# MTX_Tap_an_er_V12_Nopoti.net
KiCad netlist of a schematic drawn in EAGLE
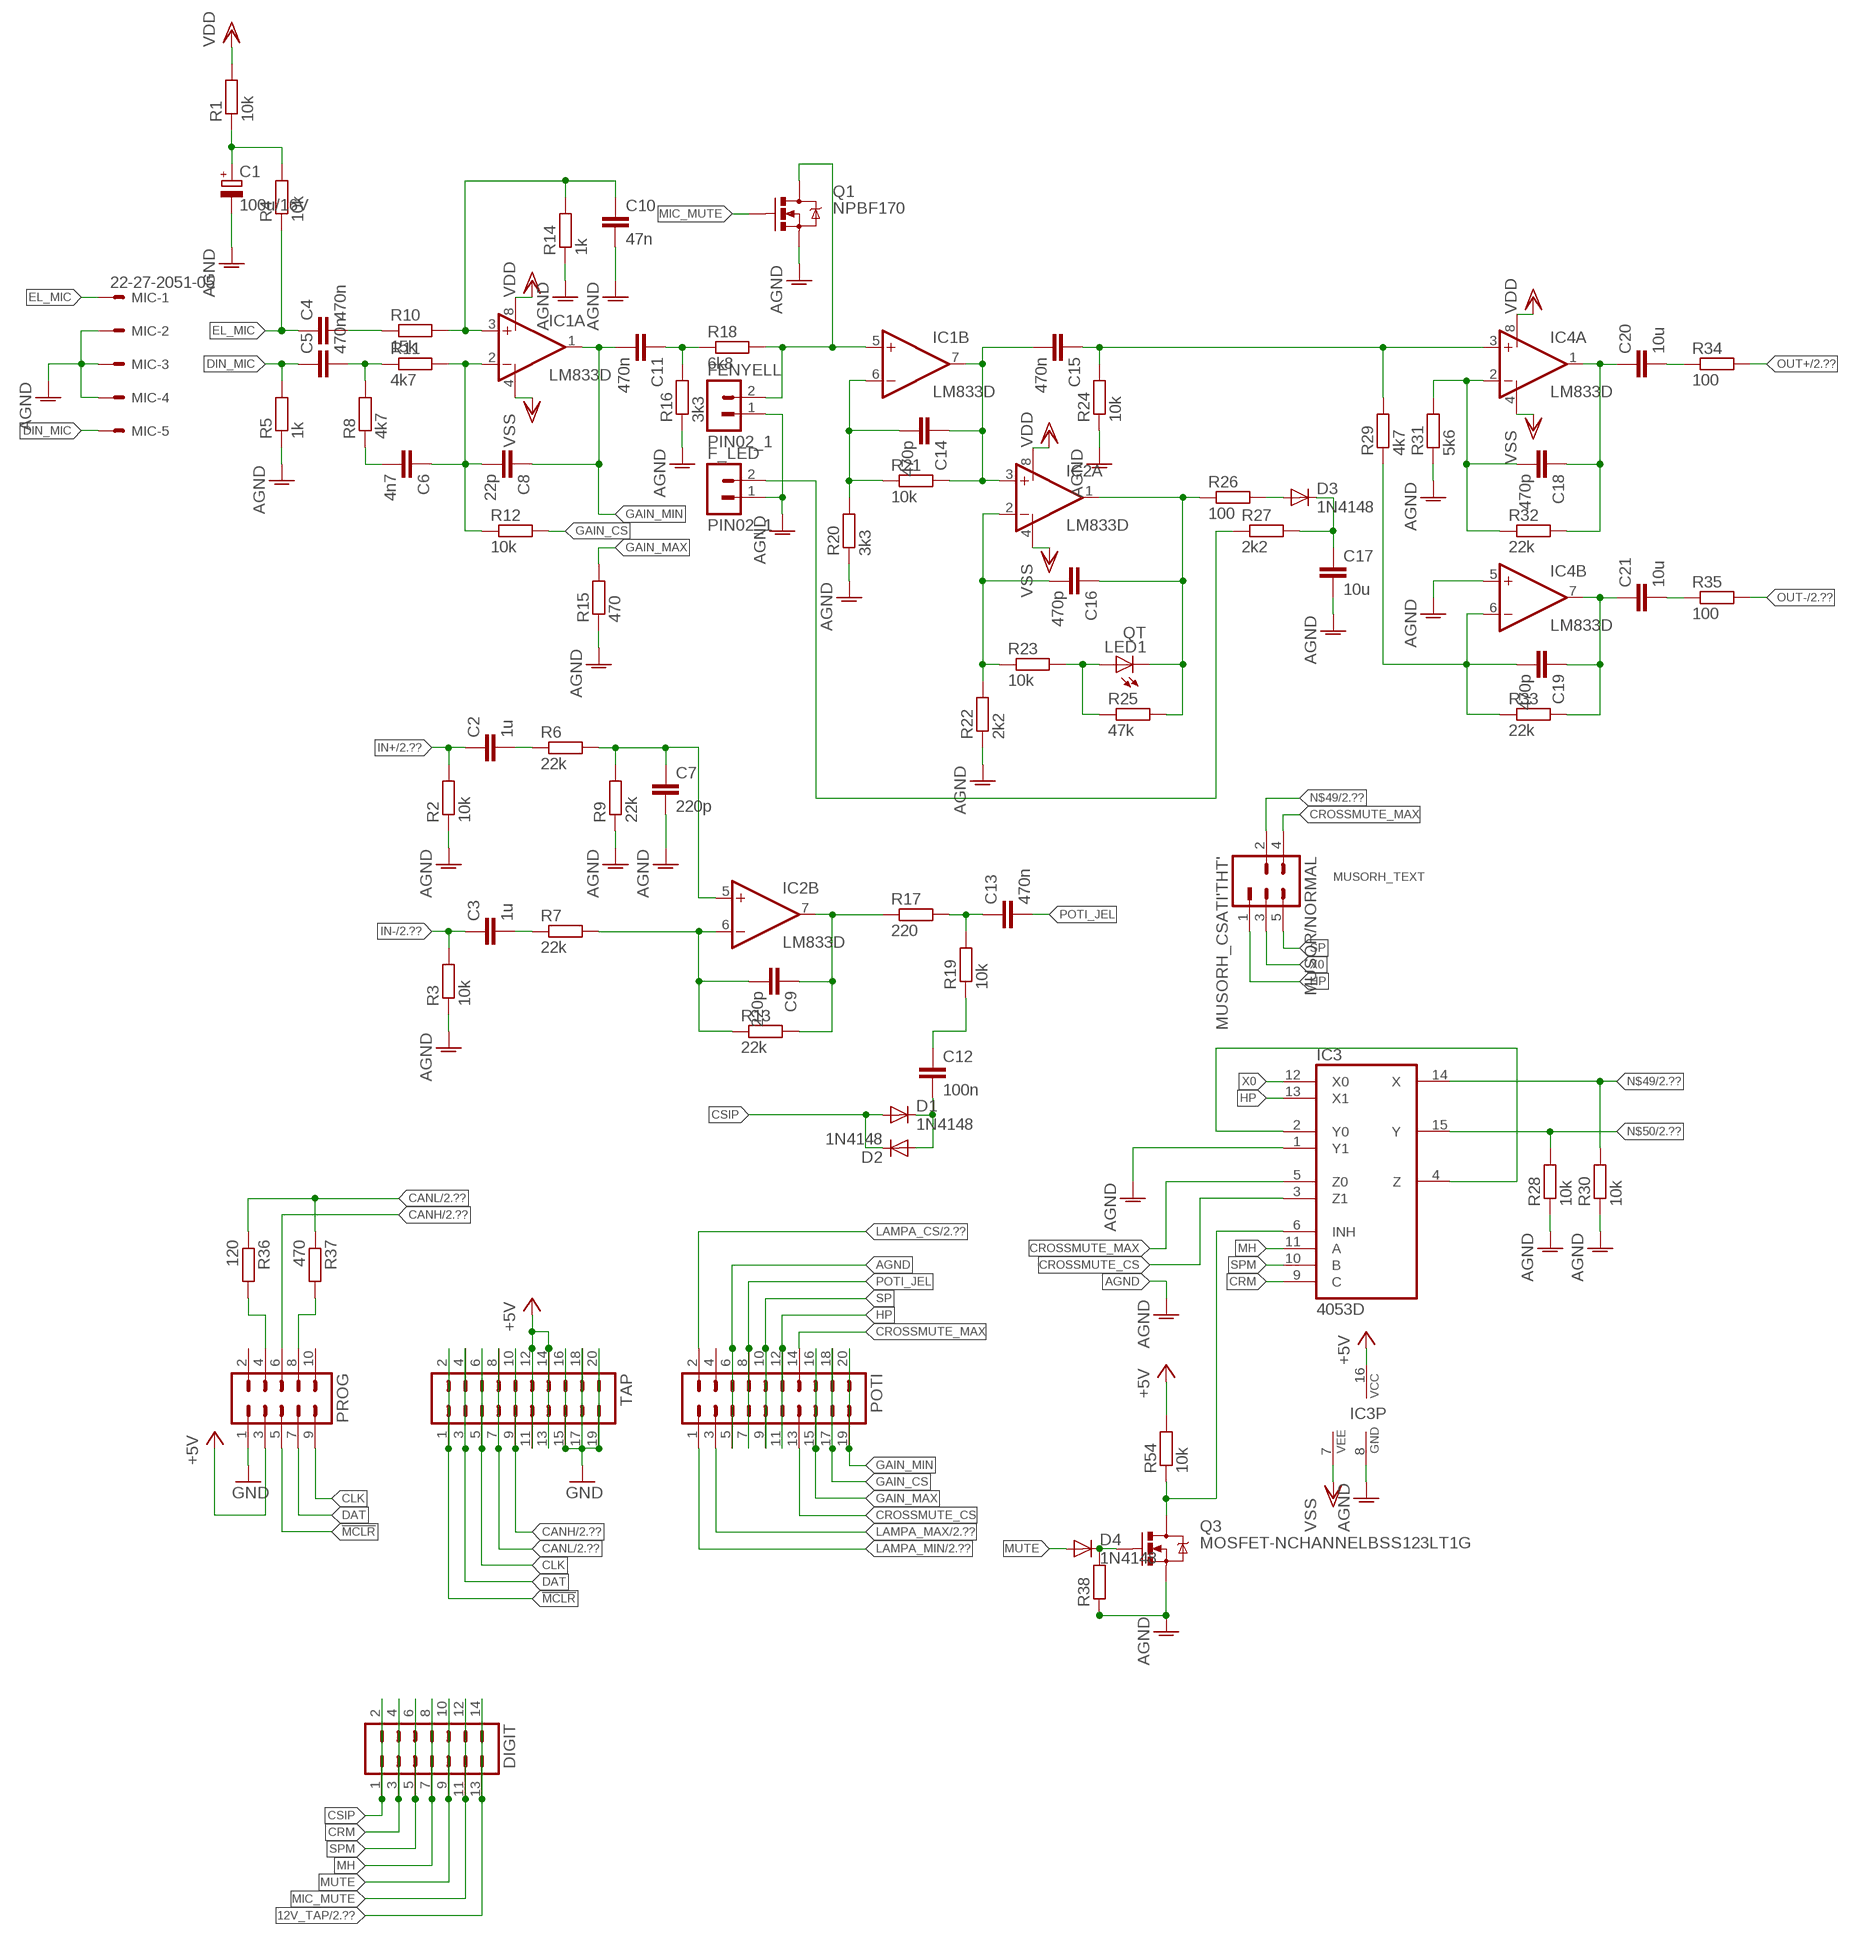
[diagram p0: schematic, sheet 1]
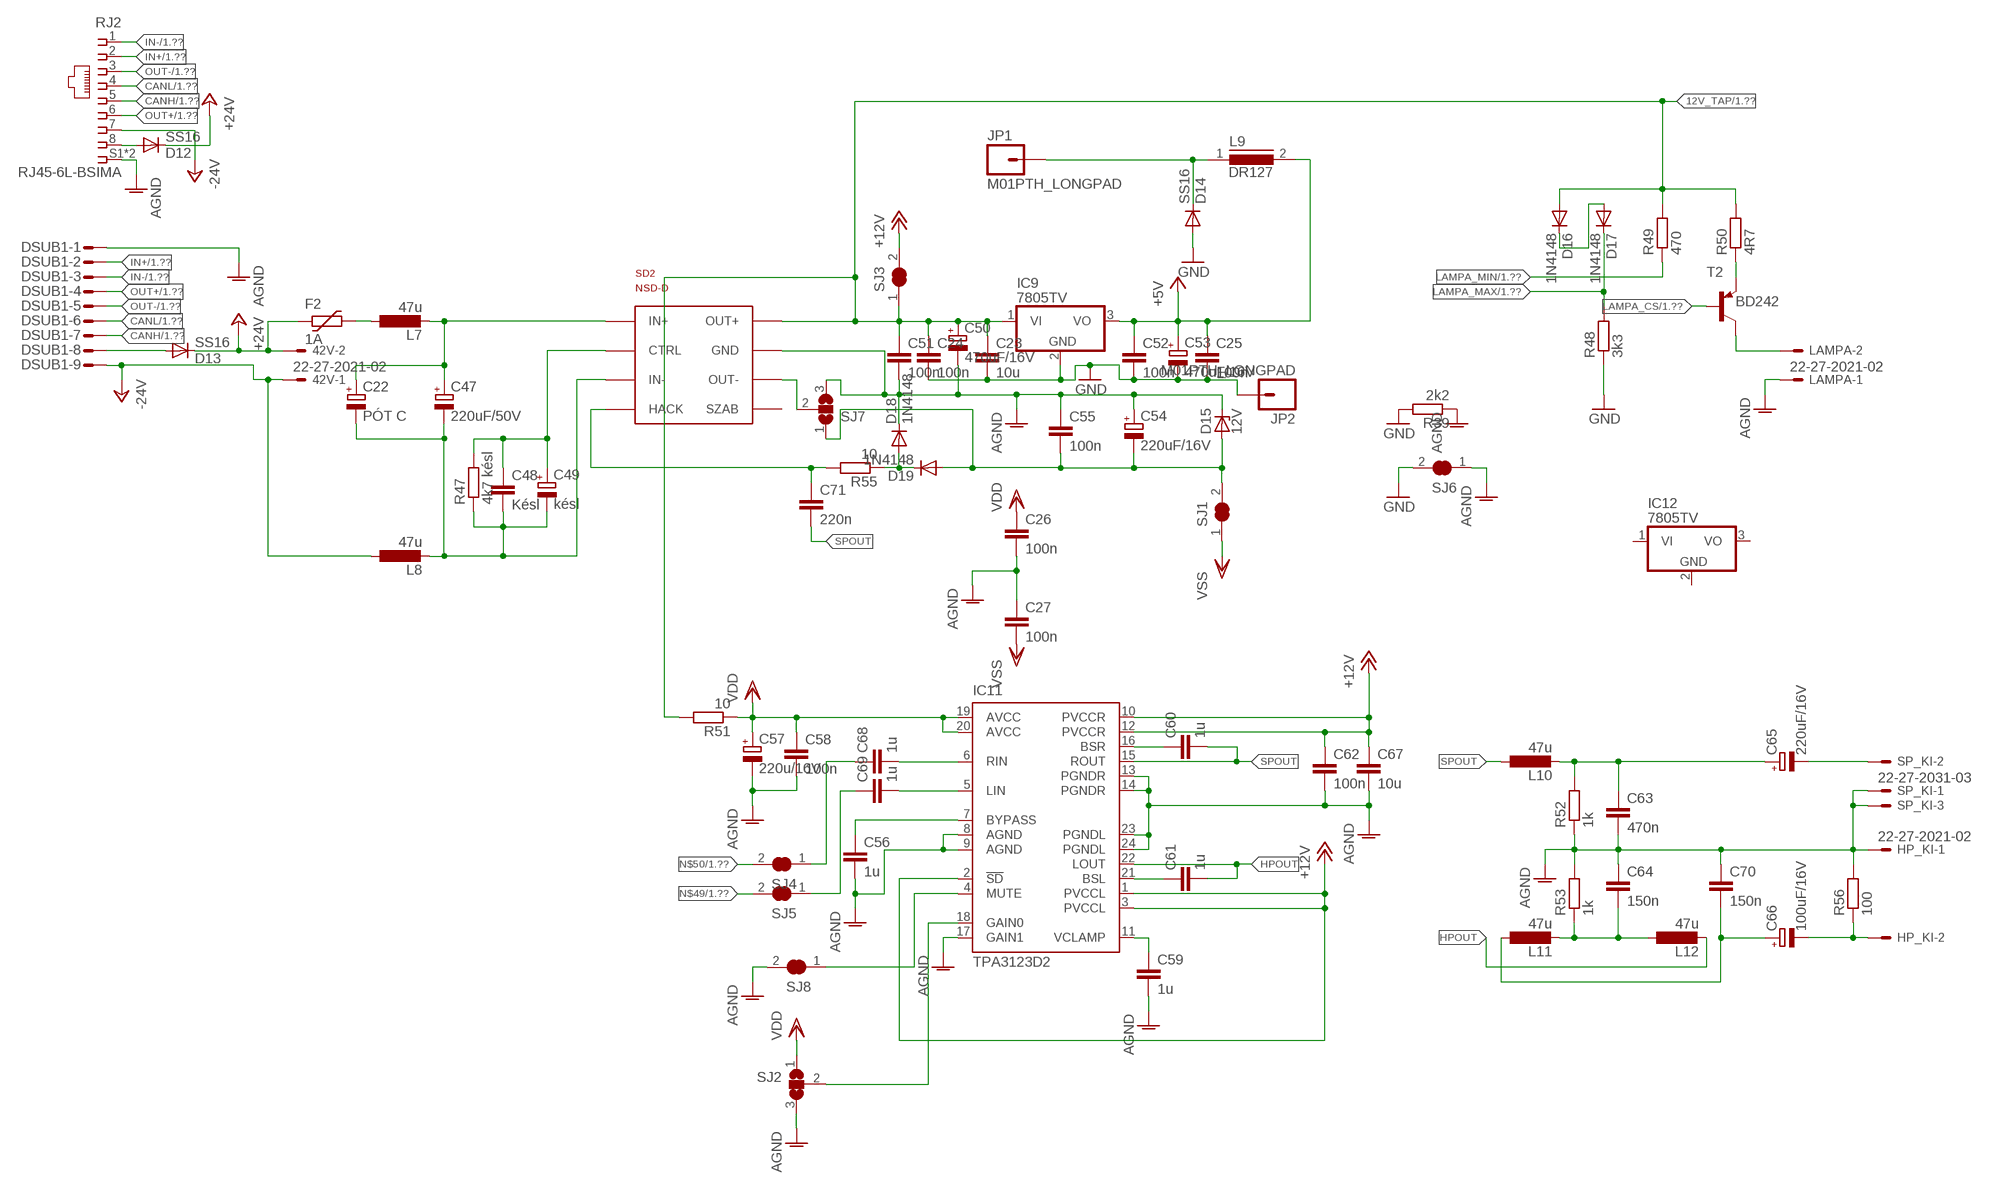
[diagram p1: schematic, sheet 2]

(export (version "E")
  (design (tool "Eeschema 10.0.6"))
  (components
    (comp (ref "C1")
      (value "100u/16V")
      (footprint "eagle-import:E2,5-5")
      (libsource (lib "eagle-import") (part "CPOL-EUE2.5-5"))
    )
    (comp (ref "C2")
      (value "1u")
      (footprint "eagle-import:C0805")
      (libsource (lib "eagle-import") (part "C-EUC0805"))
    )
    (comp (ref "C3")
      (value "1u")
      (footprint "eagle-import:C0805")
      (libsource (lib "eagle-import") (part "C-EUC0805"))
    )
    (comp (ref "C4")
      (value "470n")
      (footprint "eagle-import:C0805")
      (libsource (lib "eagle-import") (part "C-EUC0805"))
    )
    (comp (ref "C5")
      (value "470n")
      (footprint "eagle-import:C0805")
      (libsource (lib "eagle-import") (part "C-EUC0805"))
    )
    (comp (ref "C6")
      (value "4n7")
      (footprint "eagle-import:C0805")
      (libsource (lib "eagle-import") (part "C-EUC0805"))
    )
    (comp (ref "C7")
      (value "220p")
      (footprint "eagle-import:C0805")
      (libsource (lib "eagle-import") (part "C-EUC0805"))
    )
    (comp (ref "C8")
      (value "22p")
      (footprint "eagle-import:C0805")
      (libsource (lib "eagle-import") (part "C-EUC0805"))
    )
    (comp (ref "C9")
      (value "220p")
      (footprint "eagle-import:C0805")
      (libsource (lib "eagle-import") (part "C-EUC0805"))
    )
    (comp (ref "C10")
      (value "47n")
      (footprint "eagle-import:C0805")
      (libsource (lib "eagle-import") (part "C-EUC0805"))
    )
    (comp (ref "C11")
      (value "470n")
      (footprint "eagle-import:C0805")
      (libsource (lib "eagle-import") (part "C-EUC0805"))
    )
    (comp (ref "C12")
      (value "100n")
      (footprint "eagle-import:C0805")
      (libsource (lib "eagle-import") (part "C-EUC0805"))
    )
    (comp (ref "C13")
      (value "470n")
      (footprint "eagle-import:C0805")
      (libsource (lib "eagle-import") (part "C-EUC0805"))
    )
    (comp (ref "C14")
      (value "470p")
      (footprint "eagle-import:C0805")
      (libsource (lib "eagle-import") (part "C-EUC0805"))
    )
    (comp (ref "C15")
      (value "470n")
      (footprint "eagle-import:C0805")
      (libsource (lib "eagle-import") (part "C-EUC0805"))
    )
    (comp (ref "C16")
      (value "470p")
      (footprint "eagle-import:C0805")
      (libsource (lib "eagle-import") (part "C-EUC0805"))
    )
    (comp (ref "C17")
      (value "10u")
      (footprint "eagle-import:C0805")
      (libsource (lib "eagle-import") (part "C-EUC0805"))
    )
    (comp (ref "C18")
      (value "470p")
      (footprint "eagle-import:C0805")
      (libsource (lib "eagle-import") (part "C-EUC0805"))
    )
    (comp (ref "C19")
      (value "470p")
      (footprint "eagle-import:C0805")
      (libsource (lib "eagle-import") (part "C-EUC0805"))
    )
    (comp (ref "C20")
      (value "10u")
      (footprint "eagle-import:C0805")
      (libsource (lib "eagle-import") (part "C-EUC0805"))
    )
    (comp (ref "C21")
      (value "10u")
      (footprint "eagle-import:C0805")
      (libsource (lib "eagle-import") (part "C-EUC0805"))
    )
    (comp (ref "D1")
      (value "1N4148")
      (footprint "eagle-import:SOD80C")
      (libsource (lib "eagle-import") (part "DIODE-SOD80C"))
    )
    (comp (ref "D2")
      (value "1N4148")
      (footprint "eagle-import:SOD80C")
      (libsource (lib "eagle-import") (part "DIODE-SOD80C"))
    )
    (comp (ref "D3")
      (value "1N4148")
      (footprint "eagle-import:SOD80C")
      (libsource (lib "eagle-import") (part "DIODE-SOD80C"))
    )
    (comp (ref "D4")
      (value "1N4148")
      (footprint "eagle-import:SOD80C")
      (libsource (lib "eagle-import") (part "DIODE-SOD80C"))
    )
    (comp (ref "DIGIT")
      (value "MA07-2")
      (footprint "eagle-import:MA07-2")
      (libsource (lib "eagle-import") (part "MA07-2"))
    )
    (comp (ref "FENYELL")
      (value "PIN02_1")
      (footprint "eagle-import:PIN02_1")
      (libsource (lib "eagle-import") (part "PIN02_1"))
    )
    (comp (ref "F_LED")
      (value "PIN02_1")
      (footprint "eagle-import:PIN02_1")
      (libsource (lib "eagle-import") (part "PIN02_1"))
    )
    (comp (ref "IC1")
      (value "LM833D")
      (footprint "eagle-import:SO08")
      (libsource (lib "eagle-import") (part "LM833D"))
    )
    (comp (ref "IC2")
      (value "LM833D")
      (footprint "eagle-import:SO08")
      (libsource (lib "eagle-import") (part "LM833D"))
    )
    (comp (ref "IC3")
      (value "4053D")
      (footprint "eagle-import:SO16")
      (libsource (lib "eagle-import") (part "4053D"))
    )
    (comp (ref "IC4")
      (value "LM833D")
      (footprint "eagle-import:SO08")
      (libsource (lib "eagle-import") (part "LM833D"))
    )
    (comp (ref "LED1")
      (value "QT")
      (footprint "eagle-import:LED3MM")
      (libsource (lib "eagle-import") (part "LED3MM"))
    )
    (comp (ref "MIC")
      (value "22-27-2051-05")
      (footprint "eagle-import:6410-05")
      (libsource (lib "eagle-import") (part "22-?-0527-2051"))
    )
    (comp (ref "MUSOR/NORMAL")
      (value "MUSORH_CSATI'THT'")
      (footprint "eagle-import:MUSORH_CSATI")
      (libsource (lib "eagle-import") (part "MUSORH_CSATI'THT'"))
    )
    (comp (ref "POTI")
      (value "MA10-2")
      (footprint "eagle-import:MA10-2")
      (libsource (lib "eagle-import") (part "MA10-2"))
    )
    (comp (ref "PROG")
      (value "ML10L")
      (footprint "eagle-import:ML10L")
      (libsource (lib "eagle-import") (part "ML10L"))
    )
    (comp (ref "Q1")
      (value "NPBF170")
      (footprint "eagle-import:SOT23")
      (libsource (lib "eagle-import") (part "MOSFET-NCHANNELBSS138"))
    )
    (comp (ref "Q3")
      (value "MOSFET-NCHANNELBSS123LT1G")
      (footprint "eagle-import:SOT23")
      (libsource (lib "eagle-import") (part "MOSFET-NCHANNELBSS123LT1G"))
    )
    (comp (ref "R1")
      (value "10k")
      (footprint "eagle-import:R0805")
      (libsource (lib "eagle-import") (part "R-EU_R0805"))
    )
    (comp (ref "R2")
      (value "10k")
      (footprint "eagle-import:R0805")
      (libsource (lib "eagle-import") (part "R-EU_R0805"))
    )
    (comp (ref "R3")
      (value "10k")
      (footprint "eagle-import:R0805")
      (libsource (lib "eagle-import") (part "R-EU_R0805"))
    )
    (comp (ref "R4")
      (value "10k")
      (footprint "eagle-import:R0805")
      (libsource (lib "eagle-import") (part "R-EU_R0805"))
    )
    (comp (ref "R5")
      (value "1k")
      (footprint "eagle-import:R0805")
      (libsource (lib "eagle-import") (part "R-EU_R0805"))
    )
    (comp (ref "R6")
      (value "22k")
      (footprint "eagle-import:R0805")
      (libsource (lib "eagle-import") (part "R-EU_R0805"))
    )
    (comp (ref "R7")
      (value "22k")
      (footprint "eagle-import:R0805")
      (libsource (lib "eagle-import") (part "R-EU_R0805"))
    )
    (comp (ref "R8")
      (value "4k7")
      (footprint "eagle-import:R0805")
      (libsource (lib "eagle-import") (part "R-EU_R0805"))
    )
    (comp (ref "R9")
      (value "22k")
      (footprint "eagle-import:R0805")
      (libsource (lib "eagle-import") (part "R-EU_R0805"))
    )
    (comp (ref "R10")
      (value "15k")
      (footprint "eagle-import:R0805")
      (libsource (lib "eagle-import") (part "R-EU_R0805"))
    )
    (comp (ref "R11")
      (value "4k7")
      (footprint "eagle-import:R0805")
      (libsource (lib "eagle-import") (part "R-EU_R0805"))
    )
    (comp (ref "R12")
      (value "10k")
      (footprint "eagle-import:R0805")
      (libsource (lib "eagle-import") (part "R-EU_R0805"))
    )
    (comp (ref "R13")
      (value "22k")
      (footprint "eagle-import:R0805")
      (libsource (lib "eagle-import") (part "R-EU_R0805"))
    )
    (comp (ref "R14")
      (value "1k")
      (footprint "eagle-import:R0805")
      (libsource (lib "eagle-import") (part "R-EU_R0805"))
    )
    (comp (ref "R15")
      (value "470")
      (footprint "eagle-import:R0805")
      (libsource (lib "eagle-import") (part "R-EU_R0805"))
    )
    (comp (ref "R16")
      (value "3k3")
      (footprint "eagle-import:R0805")
      (libsource (lib "eagle-import") (part "R-EU_R0805"))
    )
    (comp (ref "R17")
      (value "220")
      (footprint "eagle-import:R0805")
      (libsource (lib "eagle-import") (part "R-EU_R0805"))
    )
    (comp (ref "R18")
      (value "6k8")
      (footprint "eagle-import:R0805")
      (libsource (lib "eagle-import") (part "R-EU_R0805"))
    )
    (comp (ref "R19")
      (value "10k")
      (footprint "eagle-import:R0805")
      (libsource (lib "eagle-import") (part "R-EU_R0805"))
    )
    (comp (ref "R20")
      (value "3k3")
      (footprint "eagle-import:R0805")
      (libsource (lib "eagle-import") (part "R-EU_R0805"))
    )
    (comp (ref "R21")
      (value "10k")
      (footprint "eagle-import:R0805")
      (libsource (lib "eagle-import") (part "R-EU_R0805"))
    )
    (comp (ref "R22")
      (value "2k2")
      (footprint "eagle-import:R0805")
      (libsource (lib "eagle-import") (part "R-EU_R0805"))
    )
    (comp (ref "R23")
      (value "10k")
      (footprint "eagle-import:R0805")
      (libsource (lib "eagle-import") (part "R-EU_R0805"))
    )
    (comp (ref "R24")
      (value "10k")
      (footprint "eagle-import:R0805")
      (libsource (lib "eagle-import") (part "R-EU_R0805"))
    )
    (comp (ref "R25")
      (value "47k")
      (footprint "eagle-import:R0805")
      (libsource (lib "eagle-import") (part "R-EU_R0805"))
    )
    (comp (ref "R26")
      (value "100")
      (footprint "eagle-import:R0805")
      (libsource (lib "eagle-import") (part "R-EU_R0805"))
    )
    (comp (ref "R27")
      (value "2k2")
      (footprint "eagle-import:R0805")
      (libsource (lib "eagle-import") (part "R-EU_R0805"))
    )
    (comp (ref "R28")
      (value "10k")
      (footprint "eagle-import:R0805")
      (libsource (lib "eagle-import") (part "R-EU_R0805"))
    )
    (comp (ref "R29")
      (value "4k7")
      (footprint "eagle-import:R0805")
      (libsource (lib "eagle-import") (part "R-EU_R0805"))
    )
    (comp (ref "R30")
      (value "10k")
      (footprint "eagle-import:R0805")
      (libsource (lib "eagle-import") (part "R-EU_R0805"))
    )
    (comp (ref "R31")
      (value "5k6")
      (footprint "eagle-import:R0805")
      (libsource (lib "eagle-import") (part "R-EU_R0805"))
    )
    (comp (ref "R32")
      (value "22k")
      (footprint "eagle-import:R0805")
      (libsource (lib "eagle-import") (part "R-EU_R0805"))
    )
    (comp (ref "R33")
      (value "22k")
      (footprint "eagle-import:R0805")
      (libsource (lib "eagle-import") (part "R-EU_R0805"))
    )
    (comp (ref "R34")
      (value "100")
      (footprint "eagle-import:R0805")
      (libsource (lib "eagle-import") (part "R-EU_R0805"))
    )
    (comp (ref "R35")
      (value "100")
      (footprint "eagle-import:R0805")
      (libsource (lib "eagle-import") (part "R-EU_R0805"))
    )
    (comp (ref "R36")
      (value "120")
      (footprint "eagle-import:R0805")
      (libsource (lib "eagle-import") (part "R-EU_R0805"))
    )
    (comp (ref "R37")
      (value "470")
      (footprint "eagle-import:R0805")
      (libsource (lib "eagle-import") (part "R-EU_R0805"))
    )
    (comp (ref "R38")
      (value "R-EU_R0805")
      (footprint "eagle-import:R0805")
      (libsource (lib "eagle-import") (part "R-EU_R0805"))
    )
    (comp (ref "R54")
      (value "10k")
      (footprint "eagle-import:R0805")
      (libsource (lib "eagle-import") (part "R-EU_R0805"))
    )
    (comp (ref "TAP")
      (value "MA10-2")
      (footprint "eagle-import:MA10-2")
      (libsource (lib "eagle-import") (part "MA10-2"))
    )
    (comp (ref "U$1")
      (value "MUSORH_TEXT")
      (footprint "eagle-import:MUSORH_TEXT")
      (libsource (lib "eagle-import") (part "MUSORH_TEXT"))
    )
    (comp (ref "42V")
      (value "22-27-2021-02")
      (footprint "eagle-import:6410-02")
      (libsource (lib "eagle-import") (part "22-?-0227-2021"))
    )
    (comp (ref "C22")
      (value "PÓT C")
      (footprint "eagle-import:E3,5-8")
      (libsource (lib "eagle-import") (part "CPOL-EUE3.5-8"))
    )
    (comp (ref "C23")
      (value "10u")
      (footprint "eagle-import:C0805")
      (libsource (lib "eagle-import") (part "C-EUC0805"))
    )
    (comp (ref "C24")
      (value "100n")
      (footprint "eagle-import:C0805")
      (libsource (lib "eagle-import") (part "C-EUC0805"))
    )
    (comp (ref "C25")
      (value "100n")
      (footprint "eagle-import:C0805")
      (libsource (lib "eagle-import") (part "C-EUC0805"))
    )
    (comp (ref "C26")
      (value "100n")
      (footprint "eagle-import:C0805")
      (libsource (lib "eagle-import") (part "C-EUC0805"))
    )
    (comp (ref "C27")
      (value "100n")
      (footprint "eagle-import:C0805")
      (libsource (lib "eagle-import") (part "C-EUC0805"))
    )
    (comp (ref "C47")
      (value "220uF/50V")
      (footprint "eagle-import:E3,5-8")
      (libsource (lib "eagle-import") (part "CPOL-EUE3.5-8"))
    )
    (comp (ref "C48")
      (value "Késl")
      (footprint "eagle-import:C0805")
      (libsource (lib "eagle-import") (part "C-EUC0805"))
    )
    (comp (ref "C49")
      (value "késl")
      (footprint "eagle-import:E2,5-5")
      (libsource (lib "eagle-import") (part "CPOL-EUE2.5-5"))
    )
    (comp (ref "C50")
      (value "470uF/16V")
      (footprint "eagle-import:E3,5-8")
      (libsource (lib "eagle-import") (part "CPOL-EUE3.5-8"))
    )
    (comp (ref "C51")
      (value "100n")
      (footprint "eagle-import:C0805")
      (libsource (lib "eagle-import") (part "C-EUC0805"))
    )
    (comp (ref "C52")
      (value "100n")
      (footprint "eagle-import:C0805")
      (libsource (lib "eagle-import") (part "C-EUC0805"))
    )
    (comp (ref "C53")
      (value "470uF/16V")
      (footprint "eagle-import:E3,5-8")
      (libsource (lib "eagle-import") (part "CPOL-EUE3.5-8"))
    )
    (comp (ref "C54")
      (value "220uF/16V")
      (footprint "eagle-import:E2,5-7")
      (libsource (lib "eagle-import") (part "CPOL-EUE2.5-7"))
    )
    (comp (ref "C55")
      (value "100n")
      (footprint "eagle-import:C0805")
      (libsource (lib "eagle-import") (part "C-EUC0805"))
    )
    (comp (ref "C56")
      (value "1u")
      (footprint "eagle-import:C0805")
      (libsource (lib "eagle-import") (part "C-EUC0805"))
    )
    (comp (ref "C57")
      (value "220u/16V")
      (footprint "eagle-import:E2,5-7")
      (libsource (lib "eagle-import") (part "CPOL-EUE2.5-7"))
    )
    (comp (ref "C58")
      (value "100n")
      (footprint "eagle-import:C0805")
      (libsource (lib "eagle-import") (part "C-EUC0805"))
    )
    (comp (ref "C59")
      (value "1u")
      (footprint "eagle-import:C0805")
      (libsource (lib "eagle-import") (part "C-EUC0805"))
    )
    (comp (ref "C60")
      (value "1u")
      (footprint "eagle-import:C0805")
      (libsource (lib "eagle-import") (part "C-EUC0805"))
    )
    (comp (ref "C61")
      (value "1u")
      (footprint "eagle-import:C0805")
      (libsource (lib "eagle-import") (part "C-EUC0805"))
    )
    (comp (ref "C62")
      (value "100n")
      (footprint "eagle-import:C0805")
      (libsource (lib "eagle-import") (part "C-EUC0805"))
    )
    (comp (ref "C63")
      (value "470n")
      (footprint "eagle-import:C0805")
      (libsource (lib "eagle-import") (part "C-EUC0805"))
    )
    (comp (ref "C64")
      (value "150n")
      (footprint "eagle-import:C0805")
      (libsource (lib "eagle-import") (part "C-EUC0805"))
    )
    (comp (ref "C65")
      (value "220uF/16V")
      (footprint "eagle-import:E2,5-7")
      (libsource (lib "eagle-import") (part "CPOL-EUE2.5-7"))
    )
    (comp (ref "C66")
      (value "100uF/16V")
      (footprint "eagle-import:E2,5-6")
      (libsource (lib "eagle-import") (part "CPOL-EUE2.5-6"))
    )
    (comp (ref "C67")
      (value "10u")
      (footprint "eagle-import:C0805")
      (libsource (lib "eagle-import") (part "C-EUC0805"))
    )
    (comp (ref "C68")
      (value "1u")
      (footprint "eagle-import:C0805")
      (libsource (lib "eagle-import") (part "C-EUC0805"))
    )
    (comp (ref "C69")
      (value "1u")
      (footprint "eagle-import:C0805")
      (libsource (lib "eagle-import") (part "C-EUC0805"))
    )
    (comp (ref "C70")
      (value "150n")
      (footprint "eagle-import:C0805")
      (libsource (lib "eagle-import") (part "C-EUC0805"))
    )
    (comp (ref "C71")
      (value "220n")
      (footprint "eagle-import:C0805")
      (libsource (lib "eagle-import") (part "C-EUC0805"))
    )
    (comp (ref "D12")
      (value "SS16")
      (footprint "eagle-import:DO-214AC")
      (libsource (lib "eagle-import") (part "dp_devices_DIODE-DO-214AC"))
    )
    (comp (ref "D13")
      (value "SS16")
      (footprint "eagle-import:DO-214AC")
      (libsource (lib "eagle-import") (part "dp_devices_DIODE-DO-214AC"))
    )
    (comp (ref "D14")
      (value "SS16")
      (footprint "eagle-import:DO-214AC")
      (libsource (lib "eagle-import") (part "dp_devices_DIODE-DO-214AC"))
    )
    (comp (ref "D15")
      (value "12V")
      (footprint "eagle-import:SOD80C")
      (libsource (lib "eagle-import") (part "ZENER-DIODESOD80C"))
    )
    (comp (ref "D16")
      (value "1N4148")
      (footprint "eagle-import:SOD80C")
      (libsource (lib "eagle-import") (part "DIODE-SOD80C"))
    )
    (comp (ref "D17")
      (value "1N4148")
      (footprint "eagle-import:SOD80C")
      (libsource (lib "eagle-import") (part "DIODE-SOD80C"))
    )
    (comp (ref "D18")
      (value "1N4148")
      (footprint "eagle-import:SOD80C")
      (libsource (lib "eagle-import") (part "DIODE-SOD80C"))
    )
    (comp (ref "D19")
      (value "1N4148")
      (footprint "eagle-import:SOD80C")
      (libsource (lib "eagle-import") (part "DIODE-SOD80C"))
    )
    (comp (ref "DSUB1")
      (value "M09-182S")
      (footprint "eagle-import:182-009-MALE")
      (libsource (lib "eagle-import") (part "M09?S-182"))
    )
    (comp (ref "F2")
      (value "1A")
      (footprint "eagle-import:PTC1812L")
      (libsource (lib "eagle-import") (part "FUSE_PTC-1812"))
    )
    (comp (ref "HP_KI")
      (value "22-27-2021-02")
      (footprint "eagle-import:6410-02")
      (libsource (lib "eagle-import") (part "22-?-0227-2021"))
    )
    (comp (ref "IC9")
      (value "7805TV")
      (footprint "eagle-import:TO220V")
      (libsource (lib "eagle-import") (part "78TV05"))
    )
    (comp (ref "IC11")
      (value "TPA3123D2")
      (footprint "eagle-import:PWP-TSSOP24")
      (fields (field (name "MPN") "TPA3123D2PWP"))
      (libsource (lib "eagle-import") (part "TPA3123D2"))
    )
    (comp (ref "IC12")
      (value "7805TV")
      (footprint "eagle-import:TO220V")
      (libsource (lib "eagle-import") (part "78TV05"))
    )
    (comp (ref "JP1")
      (value "M01PTH_LONGPAD")
      (footprint "eagle-import:1X01_LONGPAD")
      (libsource (lib "eagle-import") (part "M01PTH_LONGPAD"))
    )
    (comp (ref "JP2")
      (value "M01PTH_LONGPAD")
      (footprint "eagle-import:1X01_LONGPAD")
      (libsource (lib "eagle-import") (part "M01PTH_LONGPAD"))
    )
    (comp (ref "L7")
      (value "47u")
      (footprint "eagle-import:PIS2816")
      (libsource (lib "eagle-import") (part "L-EUPIS2816"))
    )
    (comp (ref "L8")
      (value "47u")
      (footprint "eagle-import:PIS2816")
      (libsource (lib "eagle-import") (part "L-EUPIS2816"))
    )
    (comp (ref "L9")
      (value "DR127")
      (footprint "eagle-import:DR127")
      (libsource (lib "eagle-import") (part "DR127"))
    )
    (comp (ref "L10")
      (value "47u")
      (footprint "eagle-import:PIS2816")
      (libsource (lib "eagle-import") (part "L-EUPIS2816"))
    )
    (comp (ref "L11")
      (value "47u")
      (footprint "eagle-import:PIS2816")
      (libsource (lib "eagle-import") (part "L-EUPIS2816"))
    )
    (comp (ref "L12")
      (value "47u")
      (footprint "eagle-import:PIS2816")
      (libsource (lib "eagle-import") (part "L-EUPIS2816"))
    )
    (comp (ref "LAMPA")
      (value "22-27-2021-02")
      (footprint "eagle-import:6410-02")
      (libsource (lib "eagle-import") (part "22-?-0227-2021"))
    )
    (comp (ref "R39")
      (value "2k2")
      (footprint "eagle-import:R0805")
      (libsource (lib "eagle-import") (part "R-EU_R0805"))
    )
    (comp (ref "R47")
      (value "4k7 késl")
      (footprint "eagle-import:R0805")
      (libsource (lib "eagle-import") (part "R-EU_R0805"))
    )
    (comp (ref "R48")
      (value "3k3")
      (footprint "eagle-import:R0805")
      (libsource (lib "eagle-import") (part "R-EU_R0805"))
    )
    (comp (ref "R49")
      (value "470")
      (footprint "eagle-import:R0805")
      (libsource (lib "eagle-import") (part "R-EU_R0805"))
    )
    (comp (ref "R50")
      (value "4R7")
      (footprint "eagle-import:R0805")
      (libsource (lib "eagle-import") (part "R-EU_R0805"))
    )
    (comp (ref "R51")
      (value "10")
      (footprint "eagle-import:R1210")
      (libsource (lib "eagle-import") (part "R-EU_R1210"))
    )
    (comp (ref "R52")
      (value "1k")
      (footprint "eagle-import:R0805")
      (libsource (lib "eagle-import") (part "R-EU_R0805"))
    )
    (comp (ref "R53")
      (value "1k")
      (footprint "eagle-import:R0805")
      (libsource (lib "eagle-import") (part "R-EU_R0805"))
    )
    (comp (ref "R55")
      (value "10")
      (footprint "eagle-import:R0805")
      (libsource (lib "eagle-import") (part "R-EU_R0805"))
    )
    (comp (ref "R56")
      (value "100")
      (footprint "eagle-import:R0805")
      (libsource (lib "eagle-import") (part "R-EU_R0805"))
    )
    (comp (ref "RJ2")
      (value "RJ45-6L-BSIMA")
      (footprint "eagle-import:RJ45")
      (fields (field (name "MPN") "RJ45-6L-B"))
      (libsource (lib "eagle-import") (part "RJ45SIMA-6L-B"))
    )
    (comp (ref "SD2")
      (value "NSD-D")
      (footprint "eagle-import:NSD-D")
      (libsource (lib "eagle-import") (part "NSD-D"))
    )
    (comp (ref "SJ1")
      (value "SOLDERJUMPER_CLOSED")
      (footprint "eagle-import:SOLDERJUMPER_CLOSEDWIRE")
      (libsource (lib "eagle-import") (part "SOLDERJUMPER_CLOSED"))
    )
    (comp (ref "SJ2")
      (value "SJ2WW12")
      (footprint "eagle-import:SJ_2W_12")
      (libsource (lib "eagle-import") (part "SJ2WW12"))
    )
    (comp (ref "SJ3")
      (value "SOLDERJUMPER_CLOSED")
      (footprint "eagle-import:SOLDERJUMPER_CLOSEDWIRE")
      (libsource (lib "eagle-import") (part "SOLDERJUMPER_CLOSED"))
    )
    (comp (ref "SJ4")
      (value "SOLDERJUMPER_CLOSED")
      (footprint "eagle-import:SOLDERJUMPER_CLOSEDWIRE")
      (libsource (lib "eagle-import") (part "SOLDERJUMPER_CLOSED"))
    )
    (comp (ref "SJ5")
      (value "SOLDERJUMPER_CLOSED")
      (footprint "eagle-import:SOLDERJUMPER_CLOSEDWIRE")
      (libsource (lib "eagle-import") (part "SOLDERJUMPER_CLOSED"))
    )
    (comp (ref "SJ6")
      (value "SOLDERJUMPER_CLOSED")
      (footprint "eagle-import:SOLDERJUMPER_CLOSEDWIRE")
      (libsource (lib "eagle-import") (part "SOLDERJUMPER_CLOSED"))
    )
    (comp (ref "SJ7")
      (value "SJ2WW23")
      (footprint "eagle-import:SJ_2W_23")
      (libsource (lib "eagle-import") (part "SJ2WW23"))
    )
    (comp (ref "SJ8")
      (value "SOLDERJUMPER_CLOSED")
      (footprint "eagle-import:SOLDERJUMPER_CLOSEDWIRE")
      (libsource (lib "eagle-import") (part "SOLDERJUMPER_CLOSED"))
    )
    (comp (ref "SP_KI")
      (value "22-27-2031-03")
      (footprint "eagle-import:6410-03")
      (libsource (lib "eagle-import") (part "22-?-0327-2031"))
    )
    (comp (ref "T2")
      (value "BD242")
      (footprint "eagle-import:TO220V")
      (libsource (lib "eagle-import") (part "-PNP-TO220V"))
    )
  )
  (nets
    (net (code "1") (name "+5V") (class "Default")
      (node (ref "C25") (pin "1") (pinfunction "1_1") (pintype "passive"))
      (node (ref "C52") (pin "1") (pinfunction "1_1") (pintype "passive"))
      (node (ref "C53") (pin "+") (pinfunction "+_+") (pintype "passive"))
      (node (ref "IC3") (pin "16") (pinfunction "VCC_16") (pintype "power_in"))
      (node (ref "IC9") (pin "3") (pinfunction "VO_3") (pintype "passive"))
      (node (ref "L9") (pin "2") (pinfunction "2_2") (pintype "passive"))
      (node (ref "PROG") (pin "3") (pinfunction "3_3") (pintype "passive"))
      (node (ref "R54") (pin "2") (pinfunction "2_2") (pintype "passive"))
      (node (ref "TAP") (pin "11") (pinfunction "11_11") (pintype "passive"))
      (node (ref "TAP") (pin "12") (pinfunction "12_12") (pintype "passive"))
      (node (ref "TAP") (pin "13") (pinfunction "13_13") (pintype "passive"))
      (node (ref "TAP") (pin "14") (pinfunction "14_14") (pintype "passive"))
    )
    (net (code "2") (name "+12V") (class "Default")
      (node (ref "C62") (pin "1") (pinfunction "1_1") (pintype "passive"))
      (node (ref "C67") (pin "1") (pinfunction "1_1") (pintype "passive"))
      (node (ref "IC11") (pin "1") (pinfunction "PVCCL_1") (pintype "input"))
      (node (ref "IC11") (pin "10") (pinfunction "PVCCR_10") (pintype "input"))
      (node (ref "IC11") (pin "12") (pinfunction "PVCCR_12") (pintype "input"))
      (node (ref "IC11") (pin "2") (pinfunction "~{SD}_2") (pintype "input"))
      (node (ref "IC11") (pin "3") (pinfunction "PVCCL_3") (pintype "input"))
      (node (ref "SJ3") (pin "2") (pinfunction "2_2") (pintype "passive"))
    )
    (net (code "3") (name "+24V") (class "Default")
      (node (ref "42V") (pin "2") (pinfunction "S_2") (pintype "passive"))
      (node (ref "D12") (pin "1") (pinfunction "C_1") (pintype "passive"))
      (node (ref "D13") (pin "1") (pinfunction "C_1") (pintype "passive"))
      (node (ref "F2") (pin "1") (pinfunction "1_1") (pintype "passive"))
    )
    (net (code "4") (name "-24V") (class "Default")
      (node (ref "42V") (pin "1") (pinfunction "S_1") (pintype "passive"))
      (node (ref "DSUB1") (pin "9") (pinfunction "M_9") (pintype "passive"))
      (node (ref "L8") (pin "1") (pinfunction "1_1") (pintype "passive"))
      (node (ref "RJ2") (pin "7") (pinfunction "7_7") (pintype "passive"))
    )
    (net (code "5") (name "12V_TAP") (class "Default")
      (node (ref "C23") (pin "1") (pinfunction "1_1") (pintype "passive"))
      (node (ref "C24") (pin "1") (pinfunction "1_1") (pintype "passive"))
      (node (ref "C50") (pin "+") (pinfunction "+_+") (pintype "passive"))
      (node (ref "C51") (pin "1") (pinfunction "1_1") (pintype "passive"))
      (node (ref "D16") (pin "A") (pinfunction "A_A") (pintype "passive"))
      (node (ref "DIGIT") (pin "13") (pinfunction "13_13") (pintype "passive"))
      (node (ref "DIGIT") (pin "14") (pinfunction "14_14") (pintype "passive"))
      (node (ref "IC9") (pin "1") (pinfunction "VI_1") (pintype "input"))
      (node (ref "R49") (pin "2") (pinfunction "2_2") (pintype "passive"))
      (node (ref "R50") (pin "2") (pinfunction "2_2") (pintype "passive"))
      (node (ref "R51") (pin "2") (pinfunction "2_2") (pintype "passive"))
      (node (ref "SD2") (pin "OUT+") (pinfunction "OUT+_OUT+") (pintype "bidirectional"))
      (node (ref "SJ3") (pin "1") (pinfunction "1_1") (pintype "passive"))
    )
    (net (code "6") (name "AGND") (class "Default")
      (node (ref "C1") (pin "-") (pinfunction "-_-") (pintype "passive"))
      (node (ref "C10") (pin "2") (pinfunction "2_2") (pintype "passive"))
      (node (ref "C17") (pin "2") (pinfunction "2_2") (pintype "passive"))
      (node (ref "C26") (pin "2") (pinfunction "2_2") (pintype "passive"))
      (node (ref "C27") (pin "1") (pinfunction "1_1") (pintype "passive"))
      (node (ref "C50") (pin "-") (pinfunction "-_-") (pintype "passive"))
      (node (ref "C51") (pin "2") (pinfunction "2_2") (pintype "passive"))
      (node (ref "C54") (pin "+") (pinfunction "+_+") (pintype "passive"))
      (node (ref "C55") (pin "1") (pinfunction "1_1") (pintype "passive"))
      (node (ref "C56") (pin "2") (pinfunction "2_2") (pintype "passive"))
      (node (ref "C57") (pin "-") (pinfunction "-_-") (pintype "passive"))
      (node (ref "C58") (pin "2") (pinfunction "2_2") (pintype "passive"))
      (node (ref "C59") (pin "2") (pinfunction "2_2") (pintype "passive"))
      (node (ref "C62") (pin "2") (pinfunction "2_2") (pintype "passive"))
      (node (ref "C63") (pin "2") (pinfunction "2_2") (pintype "passive"))
      (node (ref "C64") (pin "1") (pinfunction "1_1") (pintype "passive"))
      (node (ref "C67") (pin "2") (pinfunction "2_2") (pintype "passive"))
      (node (ref "C7") (pin "2") (pinfunction "2_2") (pintype "passive"))
      (node (ref "C70") (pin "1") (pinfunction "1_1") (pintype "passive"))
      (node (ref "D15") (pin "C") (pinfunction "C_C") (pintype "passive"))
      (node (ref "D18") (pin "C") (pinfunction "C_C") (pintype "passive"))
      (node (ref "DSUB1") (pin "1") (pinfunction "M_1") (pintype "passive"))
      (node (ref "FENYELL") (pin "1") (pinfunction "1_1") (pintype "passive"))
      (node (ref "F_LED") (pin "1") (pinfunction "1_1") (pintype "passive"))
      (node (ref "HP_KI") (pin "1") (pinfunction "S_1") (pintype "passive"))
      (node (ref "IC11") (pin "13") (pinfunction "PGNDR_13") (pintype "input"))
      (node (ref "IC11") (pin "14") (pinfunction "PGNDR_14") (pintype "input"))
      (node (ref "IC11") (pin "17") (pinfunction "GAIN1_17") (pintype "input"))
      (node (ref "IC11") (pin "23") (pinfunction "PGNDL_23") (pintype "input"))
      (node (ref "IC11") (pin "24") (pinfunction "PGNDL_24") (pintype "input"))
      (node (ref "IC11") (pin "8") (pinfunction "AGND_8") (pintype "input"))
      (node (ref "IC11") (pin "9") (pinfunction "AGND_9") (pintype "input"))
      (node (ref "IC3") (pin "1") (pinfunction "Y1_1") (pintype "bidirectional"))
      (node (ref "IC3") (pin "8") (pinfunction "GND_8") (pintype "power_in"))
      (node (ref "IC4") (pin "5") (pinfunction "+IN_5") (pintype "input"))
      (node (ref "LAMPA") (pin "1") (pinfunction "S_1") (pintype "passive"))
      (node (ref "MIC") (pin "2") (pinfunction "S_2") (pintype "passive"))
      (node (ref "MIC") (pin "3") (pinfunction "S_3") (pintype "passive"))
      (node (ref "MIC") (pin "4") (pinfunction "S_4") (pintype "passive"))
      (node (ref "POTI") (pin "5") (pinfunction "5_5") (pintype "passive"))
      (node (ref "POTI") (pin "6") (pinfunction "6_6") (pintype "passive"))
      (node (ref "Q1") (pin "2") (pinfunction "S_2") (pintype "passive"))
      (node (ref "Q3") (pin "2") (pinfunction "S_2") (pintype "passive"))
      (node (ref "R14") (pin "1") (pinfunction "1_1") (pintype "passive"))
      (node (ref "R15") (pin "1") (pinfunction "1_1") (pintype "passive"))
      (node (ref "R16") (pin "1") (pinfunction "1_1") (pintype "passive"))
      (node (ref "R2") (pin "1") (pinfunction "1_1") (pintype "passive"))
      (node (ref "R20") (pin "1") (pinfunction "1_1") (pintype "passive"))
      (node (ref "R22") (pin "1") (pinfunction "1_1") (pintype "passive"))
      (node (ref "R24") (pin "1") (pinfunction "1_1") (pintype "passive"))
      (node (ref "R28") (pin "1") (pinfunction "1_1") (pintype "passive"))
      (node (ref "R3") (pin "1") (pinfunction "1_1") (pintype "passive"))
      (node (ref "R30") (pin "1") (pinfunction "1_1") (pintype "passive"))
      (node (ref "R31") (pin "1") (pinfunction "1_1") (pintype "passive"))
      (node (ref "R38") (pin "1") (pinfunction "1_1") (pintype "passive"))
      (node (ref "R39") (pin "1") (pinfunction "1_1") (pintype "passive"))
      (node (ref "R5") (pin "1") (pinfunction "1_1") (pintype "passive"))
      (node (ref "R52") (pin "1") (pinfunction "1_1") (pintype "passive"))
      (node (ref "R53") (pin "2") (pinfunction "2_2") (pintype "passive"))
      (node (ref "R56") (pin "2") (pinfunction "2_2") (pintype "passive"))
      (node (ref "R9") (pin "1") (pinfunction "1_1") (pintype "passive"))
      (node (ref "RJ2") (pin "S1") (pinfunction "S_S1") (pintype "passive"))
      (node (ref "RJ2") (pin "S2") (pinfunction "S_S2") (pintype "passive"))
      (node (ref "SD2") (pin "COMMON") (pinfunction "GND_COMMON") (pintype "bidirectional"))
      (node (ref "SJ2") (pin "3") (pinfunction "3_3") (pintype "passive"))
      (node (ref "SJ6") (pin "1") (pinfunction "1_1") (pintype "passive"))
      (node (ref "SJ7") (pin "3") (pinfunction "3_3") (pintype "passive"))
      (node (ref "SJ8") (pin "2") (pinfunction "2_2") (pintype "passive"))
      (node (ref "SP_KI") (pin "1") (pinfunction "S_1") (pintype "passive"))
      (node (ref "SP_KI") (pin "3") (pinfunction "S_3") (pintype "passive"))
    )
    (net (code "7") (name "CANH") (class "Default")
      (node (ref "DSUB1") (pin "7") (pinfunction "M_7") (pintype "passive"))
      (node (ref "PROG") (pin "6") (pinfunction "6_6") (pintype "passive"))
      (node (ref "RJ2") (pin "5") (pinfunction "5_5") (pintype "passive"))
      (node (ref "TAP") (pin "10") (pinfunction "10_10") (pintype "passive"))
      (node (ref "TAP") (pin "9") (pinfunction "9_9") (pintype "passive"))
    )
    (net (code "8") (name "CANL") (class "Default")
      (node (ref "DSUB1") (pin "6") (pinfunction "M_6") (pintype "passive"))
      (node (ref "R36") (pin "1") (pinfunction "1_1") (pintype "passive"))
      (node (ref "R37") (pin "1") (pinfunction "1_1") (pintype "passive"))
      (node (ref "RJ2") (pin "4") (pinfunction "4_4") (pintype "passive"))
      (node (ref "TAP") (pin "7") (pinfunction "7_7") (pintype "passive"))
      (node (ref "TAP") (pin "8") (pinfunction "8_8") (pintype "passive"))
    )
    (net (code "9") (name "CLK") (class "Default")
      (node (ref "PROG") (pin "9") (pinfunction "9_9") (pintype "passive"))
      (node (ref "TAP") (pin "5") (pinfunction "5_5") (pintype "passive"))
      (node (ref "TAP") (pin "6") (pinfunction "6_6") (pintype "passive"))
    )
    (net (code "10") (name "CRM") (class "Default")
      (node (ref "DIGIT") (pin "3") (pinfunction "3_3") (pintype "passive"))
      (node (ref "DIGIT") (pin "4") (pinfunction "4_4") (pintype "passive"))
      (node (ref "IC3") (pin "9") (pinfunction "C_9") (pintype "input"))
    )
    (net (code "11") (name "CROSSMUTE_CS") (class "Default")
      (node (ref "IC3") (pin "3") (pinfunction "Z1_3") (pintype "bidirectional"))
      (node (ref "POTI") (pin "13") (pinfunction "13_13") (pintype "passive"))
    )
    (net (code "12") (name "CROSSMUTE_MAX") (class "Default")
      (node (ref "IC3") (pin "5") (pinfunction "Z0_5") (pintype "bidirectional"))
      (node (ref "MUSOR/NORMAL") (pin "4") (pinfunction "4_4") (pintype "passive"))
      (node (ref "POTI") (pin "14") (pinfunction "14_14") (pintype "passive"))
    )
    (net (code "13") (name "CSIP") (class "Default")
      (node (ref "D1") (pin "A") (pinfunction "A_A") (pintype "passive"))
      (node (ref "D2") (pin "C") (pinfunction "C_C") (pintype "passive"))
      (node (ref "DIGIT") (pin "1") (pinfunction "1_1") (pintype "passive"))
      (node (ref "DIGIT") (pin "2") (pinfunction "2_2") (pintype "passive"))
    )
    (net (code "14") (name "DAT") (class "Default")
      (node (ref "PROG") (pin "7") (pinfunction "7_7") (pintype "passive"))
      (node (ref "TAP") (pin "3") (pinfunction "3_3") (pintype "passive"))
      (node (ref "TAP") (pin "4") (pinfunction "4_4") (pintype "passive"))
    )
    (net (code "15") (name "DIN_MIC") (class "Default")
      (node (ref "C5") (pin "1") (pinfunction "1_1") (pintype "passive"))
      (node (ref "MIC") (pin "5") (pinfunction "S_5") (pintype "passive"))
      (node (ref "R5") (pin "2") (pinfunction "2_2") (pintype "passive"))
    )
    (net (code "16") (name "EL_MIC") (class "Default")
      (node (ref "C4") (pin "1") (pinfunction "1_1") (pintype "passive"))
      (node (ref "MIC") (pin "1") (pinfunction "S_1") (pintype "passive"))
      (node (ref "R4") (pin "1") (pinfunction "1_1") (pintype "passive"))
    )
    (net (code "17") (name "GAIN_CS") (class "Default")
      (node (ref "POTI") (pin "17") (pinfunction "17_17") (pintype "passive"))
      (node (ref "POTI") (pin "18") (pinfunction "18_18") (pintype "passive"))
      (node (ref "R12") (pin "2") (pinfunction "2_2") (pintype "passive"))
    )
    (net (code "18") (name "GAIN_MAX") (class "Default")
      (node (ref "POTI") (pin "15") (pinfunction "15_15") (pintype "passive"))
      (node (ref "POTI") (pin "16") (pinfunction "16_16") (pintype "passive"))
      (node (ref "R15") (pin "2") (pinfunction "2_2") (pintype "passive"))
    )
    (net (code "19") (name "GAIN_MIN") (class "Default")
      (node (ref "C11") (pin "2") (pinfunction "2_2") (pintype "passive"))
      (node (ref "C8") (pin "1") (pinfunction "1_1") (pintype "passive"))
      (node (ref "IC1") (pin "1") (pinfunction "OUT_1") (pintype "output"))
      (node (ref "POTI") (pin "19") (pinfunction "19_19") (pintype "passive"))
      (node (ref "POTI") (pin "20") (pinfunction "20_20") (pintype "passive"))
    )
    (net (code "20") (name "GND") (class "Default")
      (node (ref "C23") (pin "2") (pinfunction "2_2") (pintype "passive"))
      (node (ref "C24") (pin "2") (pinfunction "2_2") (pintype "passive"))
      (node (ref "C25") (pin "2") (pinfunction "2_2") (pintype "passive"))
      (node (ref "C52") (pin "2") (pinfunction "2_2") (pintype "passive"))
      (node (ref "C53") (pin "-") (pinfunction "-_-") (pintype "passive"))
      (node (ref "D14") (pin "2") (pinfunction "A_2") (pintype "passive"))
      (node (ref "IC9") (pin "2") (pinfunction "GND_2") (pintype "passive"))
      (node (ref "JP2") (pin "1") (pinfunction "1_1") (pintype "passive"))
      (node (ref "PROG") (pin "1") (pinfunction "1_1") (pintype "passive"))
      (node (ref "R39") (pin "2") (pinfunction "2_2") (pintype "passive"))
      (node (ref "R48") (pin "1") (pinfunction "1_1") (pintype "passive"))
      (node (ref "SJ6") (pin "2") (pinfunction "2_2") (pintype "passive"))
      (node (ref "TAP") (pin "15") (pinfunction "15_15") (pintype "passive"))
      (node (ref "TAP") (pin "16") (pinfunction "16_16") (pintype "passive"))
      (node (ref "TAP") (pin "17") (pinfunction "17_17") (pintype "passive"))
      (node (ref "TAP") (pin "18") (pinfunction "18_18") (pintype "passive"))
      (node (ref "TAP") (pin "19") (pinfunction "19_19") (pintype "passive"))
      (node (ref "TAP") (pin "20") (pinfunction "20_20") (pintype "passive"))
    )
    (net (code "21") (name "HP") (class "Default")
      (node (ref "IC3") (pin "13") (pinfunction "X1_13") (pintype "bidirectional"))
      (node (ref "MUSOR/NORMAL") (pin "1") (pinfunction "1_1") (pintype "passive"))
      (node (ref "POTI") (pin "11") (pinfunction "11_11") (pintype "passive"))
      (node (ref "POTI") (pin "12") (pinfunction "12_12") (pintype "passive"))
    )
    (net (code "22") (name "HPOUT") (class "Default")
      (node (ref "C61") (pin "2") (pinfunction "2_2") (pintype "passive"))
      (node (ref "IC11") (pin "22") (pinfunction "LOUT_22") (pintype "output"))
      (node (ref "L12") (pin "2") (pinfunction "2_2") (pintype "passive"))
    )
    (net (code "23") (name "IN+") (class "Default")
      (node (ref "C2") (pin "1") (pinfunction "1_1") (pintype "passive"))
      (node (ref "DSUB1") (pin "2") (pinfunction "M_2") (pintype "passive"))
      (node (ref "R2") (pin "2") (pinfunction "2_2") (pintype "passive"))
      (node (ref "RJ2") (pin "2") (pinfunction "2_2") (pintype "passive"))
    )
    (net (code "24") (name "IN-") (class "Default")
      (node (ref "C3") (pin "1") (pinfunction "1_1") (pintype "passive"))
      (node (ref "DSUB1") (pin "3") (pinfunction "M_3") (pintype "passive"))
      (node (ref "R3") (pin "2") (pinfunction "2_2") (pintype "passive"))
      (node (ref "RJ2") (pin "1") (pinfunction "1_1") (pintype "passive"))
    )
    (net (code "25") (name "LAMPA_CS") (class "Default")
      (node (ref "POTI") (pin "2") (pinfunction "2_2") (pintype "passive"))
      (node (ref "T2") (pin "1") (pinfunction "B_1") (pintype "passive"))
    )
    (net (code "26") (name "LAMPA_MAX") (class "Default")
      (node (ref "D17") (pin "C") (pinfunction "C_C") (pintype "passive"))
      (node (ref "POTI") (pin "3") (pinfunction "3_3") (pintype "passive"))
      (node (ref "R48") (pin "2") (pinfunction "2_2") (pintype "passive"))
    )
    (net (code "27") (name "LAMPA_MIN") (class "Default")
      (node (ref "POTI") (pin "1") (pinfunction "1_1") (pintype "passive"))
      (node (ref "R49") (pin "1") (pinfunction "1_1") (pintype "passive"))
    )
    (net (code "28") (name "MH") (class "Default")
      (node (ref "DIGIT") (pin "7") (pinfunction "7_7") (pintype "passive"))
      (node (ref "DIGIT") (pin "8") (pinfunction "8_8") (pintype "passive"))
      (node (ref "IC3") (pin "11") (pinfunction "A_11") (pintype "input"))
    )
    (net (code "29") (name "MIC_MUTE") (class "Default")
      (node (ref "DIGIT") (pin "11") (pinfunction "11_11") (pintype "passive"))
      (node (ref "DIGIT") (pin "12") (pinfunction "12_12") (pintype "passive"))
      (node (ref "Q1") (pin "1") (pinfunction "G_1") (pintype "passive"))
    )
    (net (code "30") (name "MUTE") (class "Default")
      (node (ref "D4") (pin "A") (pinfunction "A_A") (pintype "passive"))
      (node (ref "DIGIT") (pin "10") (pinfunction "10_10") (pintype "passive"))
      (node (ref "DIGIT") (pin "9") (pinfunction "9_9") (pintype "passive"))
    )
    (net (code "31") (name "N$49") (class "Default")
      (node (ref "IC3") (pin "14") (pinfunction "X_14") (pintype "bidirectional"))
      (node (ref "MUSOR/NORMAL") (pin "2") (pinfunction "2_2") (pintype "passive"))
      (node (ref "R30") (pin "2") (pinfunction "2_2") (pintype "passive"))
      (node (ref "SJ5") (pin "2") (pinfunction "2_2") (pintype "passive"))
    )
    (net (code "32") (name "N$50") (class "Default")
      (node (ref "IC3") (pin "15") (pinfunction "Y_15") (pintype "bidirectional"))
      (node (ref "R28") (pin "2") (pinfunction "2_2") (pintype "passive"))
      (node (ref "SJ4") (pin "2") (pinfunction "2_2") (pintype "passive"))
    )
    (net (code "33") (name "Net-(C1-Pad+)") (class "Default")
      (node (ref "C1") (pin "+") (pinfunction "+_+") (pintype "passive"))
      (node (ref "R1") (pin "1") (pinfunction "1_1") (pintype "passive"))
      (node (ref "R4") (pin "2") (pinfunction "2_2") (pintype "passive"))
    )
    (net (code "34") (name "Net-(C2-Pad2)") (class "Default")
      (node (ref "C2") (pin "2") (pinfunction "2_2") (pintype "passive"))
      (node (ref "R6") (pin "1") (pinfunction "1_1") (pintype "passive"))
    )
    (net (code "35") (name "Net-(C3-Pad2)") (class "Default")
      (node (ref "C3") (pin "2") (pinfunction "2_2") (pintype "passive"))
      (node (ref "R7") (pin "1") (pinfunction "1_1") (pintype "passive"))
    )
    (net (code "36") (name "Net-(C4-Pad2)") (class "Default")
      (node (ref "C4") (pin "2") (pinfunction "2_2") (pintype "passive"))
      (node (ref "R10") (pin "1") (pinfunction "1_1") (pintype "passive"))
    )
    (net (code "37") (name "Net-(C5-Pad2)") (class "Default")
      (node (ref "C5") (pin "2") (pinfunction "2_2") (pintype "passive"))
      (node (ref "R11") (pin "1") (pinfunction "1_1") (pintype "passive"))
      (node (ref "R8") (pin "2") (pinfunction "2_2") (pintype "passive"))
    )
    (net (code "38") (name "Net-(C6-Pad2)") (class "Default")
      (node (ref "C6") (pin "2") (pinfunction "2_2") (pintype "passive"))
      (node (ref "R8") (pin "1") (pinfunction "1_1") (pintype "passive"))
    )
    (net (code "39") (name "Net-(C11-Pad1)") (class "Default")
      (node (ref "C11") (pin "1") (pinfunction "1_1") (pintype "passive"))
      (node (ref "R16") (pin "2") (pinfunction "2_2") (pintype "passive"))
      (node (ref "R18") (pin "1") (pinfunction "1_1") (pintype "passive"))
    )
    (net (code "40") (name "Net-(C12-Pad1)") (class "Default")
      (node (ref "C12") (pin "1") (pinfunction "1_1") (pintype "passive"))
      (node (ref "R19") (pin "1") (pinfunction "1_1") (pintype "passive"))
    )
    (net (code "41") (name "Net-(C12-Pad2)") (class "Default")
      (node (ref "C12") (pin "2") (pinfunction "2_2") (pintype "passive"))
      (node (ref "D1") (pin "C") (pinfunction "C_C") (pintype "passive"))
      (node (ref "D2") (pin "A") (pinfunction "A_A") (pintype "passive"))
    )
    (net (code "42") (name "Net-(C13-Pad1)") (class "Default")
      (node (ref "C13") (pin "1") (pinfunction "1_1") (pintype "passive"))
      (node (ref "R17") (pin "2") (pinfunction "2_2") (pintype "passive"))
      (node (ref "R19") (pin "2") (pinfunction "2_2") (pintype "passive"))
    )
    (net (code "43") (name "Net-(C17-Pad1)") (class "Default")
      (node (ref "C17") (pin "1") (pinfunction "1_1") (pintype "passive"))
      (node (ref "D3") (pin "C") (pinfunction "C_C") (pintype "passive"))
      (node (ref "R27") (pin "2") (pinfunction "2_2") (pintype "passive"))
    )
    (net (code "44") (name "Net-(C20-Pad2)") (class "Default")
      (node (ref "C20") (pin "2") (pinfunction "2_2") (pintype "passive"))
      (node (ref "R34") (pin "1") (pinfunction "1_1") (pintype "passive"))
    )
    (net (code "45") (name "Net-(C21-Pad2)") (class "Default")
      (node (ref "C21") (pin "2") (pinfunction "2_2") (pintype "passive"))
      (node (ref "R35") (pin "1") (pinfunction "1_1") (pintype "passive"))
    )
    (net (code "46") (name "Net-(C54-Pad-)") (class "Default")
      (node (ref "C54") (pin "-") (pinfunction "-_-") (pintype "passive"))
      (node (ref "C55") (pin "2") (pinfunction "2_2") (pintype "passive"))
      (node (ref "D15") (pin "A") (pinfunction "A_A") (pintype "passive"))
      (node (ref "D19") (pin "A") (pinfunction "A_A") (pintype "passive"))
      (node (ref "SJ1") (pin "2") (pinfunction "2_2") (pintype "passive"))
      (node (ref "SJ7") (pin "1") (pinfunction "1_1") (pintype "passive"))
    )
    (net (code "47") (name "Net-(C63-Pad1)") (class "Default")
      (node (ref "C63") (pin "1") (pinfunction "1_1") (pintype "passive"))
      (node (ref "C65") (pin "+") (pinfunction "+_+") (pintype "passive"))
      (node (ref "L10") (pin "2") (pinfunction "2_2") (pintype "passive"))
      (node (ref "R52") (pin "2") (pinfunction "2_2") (pintype "passive"))
    )
    (net (code "48") (name "Net-(C64-Pad2)") (class "Default")
      (node (ref "C64") (pin "2") (pinfunction "2_2") (pintype "passive"))
      (node (ref "L11") (pin "2") (pinfunction "2_2") (pintype "passive"))
      (node (ref "L12") (pin "1") (pinfunction "1_1") (pintype "passive"))
      (node (ref "R53") (pin "1") (pinfunction "1_1") (pintype "passive"))
    )
    (net (code "49") (name "Net-(C66-Pad+)") (class "Default")
      (node (ref "C66") (pin "+") (pinfunction "+_+") (pintype "passive"))
      (node (ref "C70") (pin "2") (pinfunction "2_2") (pintype "passive"))
      (node (ref "L11") (pin "1") (pinfunction "1_1") (pintype "passive"))
    )
    (net (code "50") (name "Net-(C68-Pad1)") (class "Default")
      (node (ref "C68") (pin "1") (pinfunction "1_1") (pintype "passive"))
      (node (ref "SJ4") (pin "1") (pinfunction "1_1") (pintype "passive"))
    )
    (net (code "51") (name "Net-(C69-Pad1)") (class "Default")
      (node (ref "C69") (pin "1") (pinfunction "1_1") (pintype "passive"))
      (node (ref "SJ5") (pin "1") (pinfunction "1_1") (pintype "passive"))
    )
    (net (code "52") (name "Net-(C71-Pad1)") (class "Default")
      (node (ref "C71") (pin "1") (pinfunction "1_1") (pintype "passive"))
      (node (ref "R55") (pin "2") (pinfunction "2_2") (pintype "passive"))
      (node (ref "SD2") (pin "HACK") (pinfunction "HACK_HACK") (pintype "bidirectional"))
    )
    (net (code "53") (name "Net-(D3-PadA)") (class "Default")
      (node (ref "D3") (pin "A") (pinfunction "A_A") (pintype "passive"))
      (node (ref "R26") (pin "2") (pinfunction "2_2") (pintype "passive"))
    )
    (net (code "54") (name "Net-(D12-A)") (class "Default")
      (node (ref "D12") (pin "2") (pinfunction "A_2") (pintype "passive"))
      (node (ref "RJ2") (pin "8") (pinfunction "8_8") (pintype "passive"))
    )
    (net (code "55") (name "Net-(D13-A)") (class "Default")
      (node (ref "D13") (pin "2") (pinfunction "A_2") (pintype "passive"))
      (node (ref "DSUB1") (pin "8") (pinfunction "M_8") (pintype "passive"))
    )
    (net (code "56") (name "Net-(D14-C)") (class "Default")
      (node (ref "D14") (pin "1") (pinfunction "C_1") (pintype "passive"))
      (node (ref "JP1") (pin "1") (pinfunction "1_1") (pintype "passive"))
      (node (ref "L9") (pin "1") (pinfunction "1_1") (pintype "passive"))
    )
    (net (code "57") (name "Net-(D16-PadC)") (class "Default")
      (node (ref "D16") (pin "C") (pinfunction "C_C") (pintype "passive"))
      (node (ref "D17") (pin "A") (pinfunction "A_A") (pintype "passive"))
    )
    (net (code "58") (name "Net-(D18-PadA)") (class "Default")
      (node (ref "D18") (pin "A") (pinfunction "A_A") (pintype "passive"))
      (node (ref "D19") (pin "C") (pinfunction "C_C") (pintype "passive"))
      (node (ref "R55") (pin "1") (pinfunction "1_1") (pintype "passive"))
    )
    (net (code "59") (name "Net-(F2-Pad2)") (class "Default")
      (node (ref "F2") (pin "2") (pinfunction "2_2") (pintype "passive"))
      (node (ref "L7") (pin "1") (pinfunction "1_1") (pintype "passive"))
    )
    (net (code "60") (name "Net-(F_LED-Pad2)") (class "Default")
      (node (ref "F_LED") (pin "2") (pinfunction "2_2") (pintype "passive"))
      (node (ref "R27") (pin "1") (pinfunction "1_1") (pintype "passive"))
    )
    (net (code "61") (name "Net-(HP_KIB-S)") (class "Default")
      (node (ref "C66") (pin "-") (pinfunction "-_-") (pintype "passive"))
      (node (ref "HP_KI") (pin "2") (pinfunction "S_2") (pintype "passive"))
      (node (ref "R56") (pin "1") (pinfunction "1_1") (pintype "passive"))
    )
    (net (code "62") (name "Net-(IC1A-+IN)") (class "Default")
      (node (ref "C10") (pin "1") (pinfunction "1_1") (pintype "passive"))
      (node (ref "IC1") (pin "3") (pinfunction "+IN_3") (pintype "input"))
      (node (ref "R10") (pin "2") (pinfunction "2_2") (pintype "passive"))
      (node (ref "R14") (pin "2") (pinfunction "2_2") (pintype "passive"))
    )
    (net (code "63") (name "Net-(IC1A--IN)") (class "Default")
      (node (ref "C6") (pin "1") (pinfunction "1_1") (pintype "passive"))
      (node (ref "C8") (pin "2") (pinfunction "2_2") (pintype "passive"))
      (node (ref "IC1") (pin "2") (pinfunction "-IN_2") (pintype "input"))
      (node (ref "R11") (pin "2") (pinfunction "2_2") (pintype "passive"))
      (node (ref "R12") (pin "1") (pinfunction "1_1") (pintype "passive"))
    )
    (net (code "64") (name "Net-(IC1B-+IN)") (class "Default")
      (node (ref "FENYELL") (pin "2") (pinfunction "2_2") (pintype "passive"))
      (node (ref "IC1") (pin "5") (pinfunction "+IN_5") (pintype "input"))
      (node (ref "Q1") (pin "3") (pinfunction "D_3") (pintype "passive"))
      (node (ref "R18") (pin "2") (pinfunction "2_2") (pintype "passive"))
    )
    (net (code "65") (name "Net-(IC1B--IN)") (class "Default")
      (node (ref "C14") (pin "2") (pinfunction "2_2") (pintype "passive"))
      (node (ref "IC1") (pin "6") (pinfunction "-IN_6") (pintype "input"))
      (node (ref "R20") (pin "2") (pinfunction "2_2") (pintype "passive"))
      (node (ref "R21") (pin "1") (pinfunction "1_1") (pintype "passive"))
    )
    (net (code "66") (name "Net-(IC1B-OUT)") (class "Default")
      (node (ref "C14") (pin "1") (pinfunction "1_1") (pintype "passive"))
      (node (ref "C15") (pin "2") (pinfunction "2_2") (pintype "passive"))
      (node (ref "IC1") (pin "7") (pinfunction "OUT_7") (pintype "output"))
      (node (ref "IC2") (pin "3") (pinfunction "+IN_3") (pintype "input"))
      (node (ref "R21") (pin "2") (pinfunction "2_2") (pintype "passive"))
    )
    (net (code "67") (name "Net-(IC2A--IN)") (class "Default")
      (node (ref "C16") (pin "2") (pinfunction "2_2") (pintype "passive"))
      (node (ref "IC2") (pin "2") (pinfunction "-IN_2") (pintype "input"))
      (node (ref "R22") (pin "2") (pinfunction "2_2") (pintype "passive"))
      (node (ref "R23") (pin "1") (pinfunction "1_1") (pintype "passive"))
    )
    (net (code "68") (name "Net-(IC2A-OUT)") (class "Default")
      (node (ref "C16") (pin "1") (pinfunction "1_1") (pintype "passive"))
      (node (ref "IC2") (pin "1") (pinfunction "OUT_1") (pintype "output"))
      (node (ref "LED1") (pin "K") (pinfunction "C_K") (pintype "passive"))
      (node (ref "R25") (pin "2") (pinfunction "2_2") (pintype "passive"))
      (node (ref "R26") (pin "1") (pinfunction "1_1") (pintype "passive"))
    )
    (net (code "69") (name "Net-(IC2B-+IN)") (class "Default")
      (node (ref "C7") (pin "1") (pinfunction "1_1") (pintype "passive"))
      (node (ref "IC2") (pin "5") (pinfunction "+IN_5") (pintype "input"))
      (node (ref "R6") (pin "2") (pinfunction "2_2") (pintype "passive"))
      (node (ref "R9") (pin "2") (pinfunction "2_2") (pintype "passive"))
    )
    (net (code "70") (name "Net-(IC2B--IN)") (class "Default")
      (node (ref "C9") (pin "2") (pinfunction "2_2") (pintype "passive"))
      (node (ref "IC2") (pin "6") (pinfunction "-IN_6") (pintype "input"))
      (node (ref "R13") (pin "1") (pinfunction "1_1") (pintype "passive"))
      (node (ref "R7") (pin "2") (pinfunction "2_2") (pintype "passive"))
    )
    (net (code "71") (name "Net-(IC2B-OUT)") (class "Default")
      (node (ref "C9") (pin "1") (pinfunction "1_1") (pintype "passive"))
      (node (ref "IC2") (pin "7") (pinfunction "OUT_7") (pintype "output"))
      (node (ref "R13") (pin "2") (pinfunction "2_2") (pintype "passive"))
      (node (ref "R17") (pin "1") (pinfunction "1_1") (pintype "passive"))
    )
    (net (code "72") (name "Net-(IC3A-INH)") (class "Default")
      (node (ref "IC3") (pin "6") (pinfunction "INH_6") (pintype "input"))
      (node (ref "Q3") (pin "3") (pinfunction "D_3") (pintype "passive"))
      (node (ref "R54") (pin "1") (pinfunction "1_1") (pintype "passive"))
    )
    (net (code "73") (name "Net-(IC3A-Y0)") (class "Default")
      (node (ref "IC3") (pin "2") (pinfunction "Y0_2") (pintype "bidirectional"))
      (node (ref "IC3") (pin "4") (pinfunction "Z_4") (pintype "bidirectional"))
    )
    (net (code "74") (name "Net-(IC4A-+IN)") (class "Default")
      (node (ref "C15") (pin "1") (pinfunction "1_1") (pintype "passive"))
      (node (ref "IC4") (pin "3") (pinfunction "+IN_3") (pintype "input"))
      (node (ref "R24") (pin "2") (pinfunction "2_2") (pintype "passive"))
      (node (ref "R29") (pin "2") (pinfunction "2_2") (pintype "passive"))
    )
    (net (code "75") (name "Net-(IC4A--IN)") (class "Default")
      (node (ref "C18") (pin "2") (pinfunction "2_2") (pintype "passive"))
      (node (ref "IC4") (pin "2") (pinfunction "-IN_2") (pintype "input"))
      (node (ref "R31") (pin "2") (pinfunction "2_2") (pintype "passive"))
      (node (ref "R32") (pin "1") (pinfunction "1_1") (pintype "passive"))
    )
    (net (code "76") (name "Net-(IC4A-OUT)") (class "Default")
      (node (ref "C18") (pin "1") (pinfunction "1_1") (pintype "passive"))
      (node (ref "C20") (pin "1") (pinfunction "1_1") (pintype "passive"))
      (node (ref "IC4") (pin "1") (pinfunction "OUT_1") (pintype "output"))
      (node (ref "R32") (pin "2") (pinfunction "2_2") (pintype "passive"))
    )
    (net (code "77") (name "Net-(IC4B--IN)") (class "Default")
      (node (ref "C19") (pin "2") (pinfunction "2_2") (pintype "passive"))
      (node (ref "IC4") (pin "6") (pinfunction "-IN_6") (pintype "input"))
      (node (ref "R29") (pin "1") (pinfunction "1_1") (pintype "passive"))
      (node (ref "R33") (pin "1") (pinfunction "1_1") (pintype "passive"))
    )
    (net (code "78") (name "Net-(IC4B-OUT)") (class "Default")
      (node (ref "C19") (pin "1") (pinfunction "1_1") (pintype "passive"))
      (node (ref "C21") (pin "1") (pinfunction "1_1") (pintype "passive"))
      (node (ref "IC4") (pin "7") (pinfunction "OUT_7") (pintype "output"))
      (node (ref "R33") (pin "2") (pinfunction "2_2") (pintype "passive"))
    )
    (net (code "79") (name "Net-(IC11-BSL)") (class "Default")
      (node (ref "C61") (pin "1") (pinfunction "1_1") (pintype "passive"))
      (node (ref "IC11") (pin "21") (pinfunction "BSL_21") (pintype "passive"))
    )
    (net (code "80") (name "Net-(IC11-BSR)") (class "Default")
      (node (ref "C60") (pin "1") (pinfunction "1_1") (pintype "passive"))
      (node (ref "IC11") (pin "16") (pinfunction "BSR_16") (pintype "passive"))
    )
    (net (code "81") (name "Net-(IC11-BYPASS)") (class "Default")
      (node (ref "C56") (pin "1") (pinfunction "1_1") (pintype "passive"))
      (node (ref "IC11") (pin "7") (pinfunction "BYPASS_7") (pintype "input"))
    )
    (net (code "82") (name "Net-(IC11-GAIN0)") (class "Default")
      (node (ref "IC11") (pin "18") (pinfunction "GAIN0_18") (pintype "input"))
      (node (ref "SJ2") (pin "2") (pinfunction "2_2") (pintype "passive"))
    )
    (net (code "83") (name "Net-(IC11-LIN)") (class "Default")
      (node (ref "C69") (pin "2") (pinfunction "2_2") (pintype "passive"))
      (node (ref "IC11") (pin "5") (pinfunction "LIN_5") (pintype "input"))
    )
    (net (code "84") (name "Net-(IC11-MUTE)") (class "Default")
      (node (ref "IC11") (pin "4") (pinfunction "MUTE_4") (pintype "input"))
      (node (ref "SJ8") (pin "1") (pinfunction "1_1") (pintype "passive"))
    )
    (net (code "85") (name "Net-(IC11-RIN)") (class "Default")
      (node (ref "C68") (pin "2") (pinfunction "2_2") (pintype "passive"))
      (node (ref "IC11") (pin "6") (pinfunction "RIN_6") (pintype "input"))
    )
    (net (code "86") (name "Net-(IC11-VCLAMP)") (class "Default")
      (node (ref "C59") (pin "1") (pinfunction "1_1") (pintype "passive"))
      (node (ref "IC11") (pin "11") (pinfunction "VCLAMP_11") (pintype "input"))
    )
    (net (code "87") (name "Net-(LAMPAB-S)") (class "Default")
      (node (ref "LAMPA") (pin "2") (pinfunction "S_2") (pintype "passive"))
      (node (ref "T2") (pin "2") (pinfunction "C_2") (pintype "passive"))
    )
    (net (code "88") (name "Net-(LED1-PadA)") (class "Default")
      (node (ref "LED1") (pin "A") (pinfunction "A_A") (pintype "passive"))
      (node (ref "R23") (pin "2") (pinfunction "2_2") (pintype "passive"))
      (node (ref "R25") (pin "1") (pinfunction "1_1") (pintype "passive"))
    )
    (net (code "89") (name "Net-(PROG-Pad4)") (class "Default")
      (node (ref "PROG") (pin "4") (pinfunction "4_4") (pintype "passive"))
      (node (ref "R36") (pin "2") (pinfunction "2_2") (pintype "passive"))
    )
    (net (code "90") (name "Net-(PROG-Pad8)") (class "Default")
      (node (ref "PROG") (pin "8") (pinfunction "8_8") (pintype "passive"))
      (node (ref "R37") (pin "2") (pinfunction "2_2") (pintype "passive"))
    )
    (net (code "91") (name "Net-(Q3-G)") (class "Default")
      (node (ref "D4") (pin "C") (pinfunction "C_C") (pintype "passive"))
      (node (ref "Q3") (pin "1") (pinfunction "G_1") (pintype "passive"))
      (node (ref "R38") (pin "2") (pinfunction "2_2") (pintype "passive"))
    )
    (net (code "92") (name "Net-(SD2-CTRL)") (class "Default")
      (node (ref "C48") (pin "1") (pinfunction "1_1") (pintype "passive"))
      (node (ref "C49") (pin "+") (pinfunction "+_+") (pintype "passive"))
      (node (ref "R47") (pin "2") (pinfunction "2_2") (pintype "passive"))
      (node (ref "SD2") (pin "CONTROL") (pinfunction "CTRL_CONTROL") (pintype "bidirectional"))
    )
    (net (code "93") (name "Net-(SD2-IN+)") (class "Default")
      (node (ref "C22") (pin "+") (pinfunction "+_+") (pintype "passive"))
      (node (ref "C47") (pin "+") (pinfunction "+_+") (pintype "passive"))
      (node (ref "L7") (pin "2") (pinfunction "2_2") (pintype "passive"))
      (node (ref "SD2") (pin "INPUT+") (pinfunction "IN+_INPUT+") (pintype "bidirectional"))
    )
    (net (code "94") (name "Net-(SD2-IN-)") (class "Default")
      (node (ref "C22") (pin "-") (pinfunction "-_-") (pintype "passive"))
      (node (ref "C47") (pin "-") (pinfunction "-_-") (pintype "passive"))
      (node (ref "C48") (pin "2") (pinfunction "2_2") (pintype "passive"))
      (node (ref "C49") (pin "-") (pinfunction "-_-") (pintype "passive"))
      (node (ref "L8") (pin "2") (pinfunction "2_2") (pintype "passive"))
      (node (ref "R47") (pin "1") (pinfunction "1_1") (pintype "passive"))
      (node (ref "SD2") (pin "INPUT-") (pinfunction "IN-_INPUT-") (pintype "bidirectional"))
    )
    (net (code "95") (name "Net-(SD2-PadOUT-)") (class "Default")
      (node (ref "SD2") (pin "OUT-") (pinfunction "OUT-_OUT-") (pintype "bidirectional"))
      (node (ref "SJ7") (pin "2") (pinfunction "2_2") (pintype "passive"))
    )
    (net (code "96") (name "Net-(SP_KIB-S)") (class "Default")
      (node (ref "C65") (pin "-") (pinfunction "-_-") (pintype "passive"))
      (node (ref "SP_KI") (pin "2") (pinfunction "S_2") (pintype "passive"))
    )
    (net (code "97") (name "Net-(T2-E)") (class "Default")
      (node (ref "R50") (pin "1") (pinfunction "1_1") (pintype "passive"))
      (node (ref "T2") (pin "3") (pinfunction "E_3") (pintype "passive"))
    )
    (net (code "98") (name "OUT+") (class "Default")
      (node (ref "DSUB1") (pin "4") (pinfunction "M_4") (pintype "passive"))
      (node (ref "R34") (pin "2") (pinfunction "2_2") (pintype "passive"))
      (node (ref "RJ2") (pin "6") (pinfunction "6_6") (pintype "passive"))
    )
    (net (code "99") (name "OUT-") (class "Default")
      (node (ref "DSUB1") (pin "5") (pinfunction "M_5") (pintype "passive"))
      (node (ref "R35") (pin "2") (pinfunction "2_2") (pintype "passive"))
      (node (ref "RJ2") (pin "3") (pinfunction "3_3") (pintype "passive"))
    )
    (net (code "100") (name "POTI_JEL") (class "Default")
      (node (ref "C13") (pin "2") (pinfunction "2_2") (pintype "passive"))
      (node (ref "POTI") (pin "7") (pinfunction "7_7") (pintype "passive"))
      (node (ref "POTI") (pin "8") (pinfunction "8_8") (pintype "passive"))
    )
    (net (code "101") (name "SP") (class "Default")
      (node (ref "MUSOR/NORMAL") (pin "5") (pinfunction "5_5") (pintype "passive"))
      (node (ref "POTI") (pin "10") (pinfunction "10_10") (pintype "passive"))
      (node (ref "POTI") (pin "9") (pinfunction "9_9") (pintype "passive"))
    )
    (net (code "102") (name "SPM") (class "Default")
      (node (ref "DIGIT") (pin "5") (pinfunction "5_5") (pintype "passive"))
      (node (ref "DIGIT") (pin "6") (pinfunction "6_6") (pintype "passive"))
      (node (ref "IC3") (pin "10") (pinfunction "B_10") (pintype "input"))
    )
    (net (code "103") (name "SPOUT") (class "Default")
      (node (ref "C60") (pin "2") (pinfunction "2_2") (pintype "passive"))
      (node (ref "C71") (pin "2") (pinfunction "2_2") (pintype "passive"))
      (node (ref "IC11") (pin "15") (pinfunction "ROUT_15") (pintype "output"))
      (node (ref "L10") (pin "1") (pinfunction "1_1") (pintype "passive"))
    )
    (net (code "104") (name "VDD") (class "Default")
      (node (ref "C26") (pin "1") (pinfunction "1_1") (pintype "passive"))
      (node (ref "C57") (pin "+") (pinfunction "+_+") (pintype "passive"))
      (node (ref "C58") (pin "1") (pinfunction "1_1") (pintype "passive"))
      (node (ref "IC1") (pin "8") (pinfunction "V+_8") (pintype "power_in"))
      (node (ref "IC11") (pin "19") (pinfunction "AVCC_19") (pintype "input"))
      (node (ref "IC11") (pin "20") (pinfunction "AVCC_20") (pintype "input"))
      (node (ref "IC2") (pin "8") (pinfunction "V+_8") (pintype "power_in"))
      (node (ref "IC4") (pin "8") (pinfunction "V+_8") (pintype "power_in"))
      (node (ref "R1") (pin "2") (pinfunction "2_2") (pintype "passive"))
      (node (ref "R51") (pin "1") (pinfunction "1_1") (pintype "passive"))
      (node (ref "SJ2") (pin "1") (pinfunction "1_1") (pintype "passive"))
    )
    (net (code "105") (name "VSS") (class "Default")
      (node (ref "C27") (pin "2") (pinfunction "2_2") (pintype "passive"))
      (node (ref "IC1") (pin "4") (pinfunction "V-_4") (pintype "power_in"))
      (node (ref "IC2") (pin "4") (pinfunction "V-_4") (pintype "power_in"))
      (node (ref "IC3") (pin "7") (pinfunction "VEE_7") (pintype "power_in"))
      (node (ref "IC4") (pin "4") (pinfunction "V-_4") (pintype "power_in"))
      (node (ref "SJ1") (pin "1") (pinfunction "1_1") (pintype "passive"))
    )
    (net (code "106") (name "X0") (class "Default")
      (node (ref "IC3") (pin "12") (pinfunction "X0_12") (pintype "bidirectional"))
      (node (ref "MUSOR/NORMAL") (pin "3") (pinfunction "3_3") (pintype "passive"))
    )
    (net (code "107") (name "unconnected-(IC12-GND-Pad2)") (class "Default")
      (node (ref "IC12") (pin "2") (pinfunction "GND_2") (pintype "passive"))
    )
    (net (code "108") (name "unconnected-(IC12-VI-Pad1)") (class "Default")
      (node (ref "IC12") (pin "1") (pinfunction "VI_1") (pintype "input"))
    )
    (net (code "109") (name "unconnected-(IC12-VO-Pad3)") (class "Default")
      (node (ref "IC12") (pin "3") (pinfunction "VO_3") (pintype "passive"))
    )
    (net (code "110") (name "unconnected-(POTI-Pad4)") (class "Default")
      (node (ref "POTI") (pin "4") (pinfunction "4_4") (pintype "passive"))
    )
    (net (code "111") (name "unconnected-(PROG-Pad2)") (class "Default")
      (node (ref "PROG") (pin "2") (pinfunction "2_2") (pintype "passive"))
    )
    (net (code "112") (name "unconnected-(PROG-Pad10)") (class "Default")
      (node (ref "PROG") (pin "10") (pinfunction "10_10") (pintype "passive"))
    )
    (net (code "113") (name "unconnected-(SD2-PadSZAB)") (class "Default")
      (node (ref "SD2") (pin "SZAB") (pinfunction "SZAB_SZAB") (pintype "bidirectional"))
    )
    (net (code "114") (name "~{MCLR}") (class "Default")
      (node (ref "PROG") (pin "5") (pinfunction "5_5") (pintype "passive"))
      (node (ref "TAP") (pin "1") (pinfunction "1_1") (pintype "passive"))
      (node (ref "TAP") (pin "2") (pinfunction "2_2") (pintype "passive"))
    )
  )
)
